# Capstone_Preconditioning_SchematicSheet.net
KiCad netlist of a schematic drawn in Altium Designer
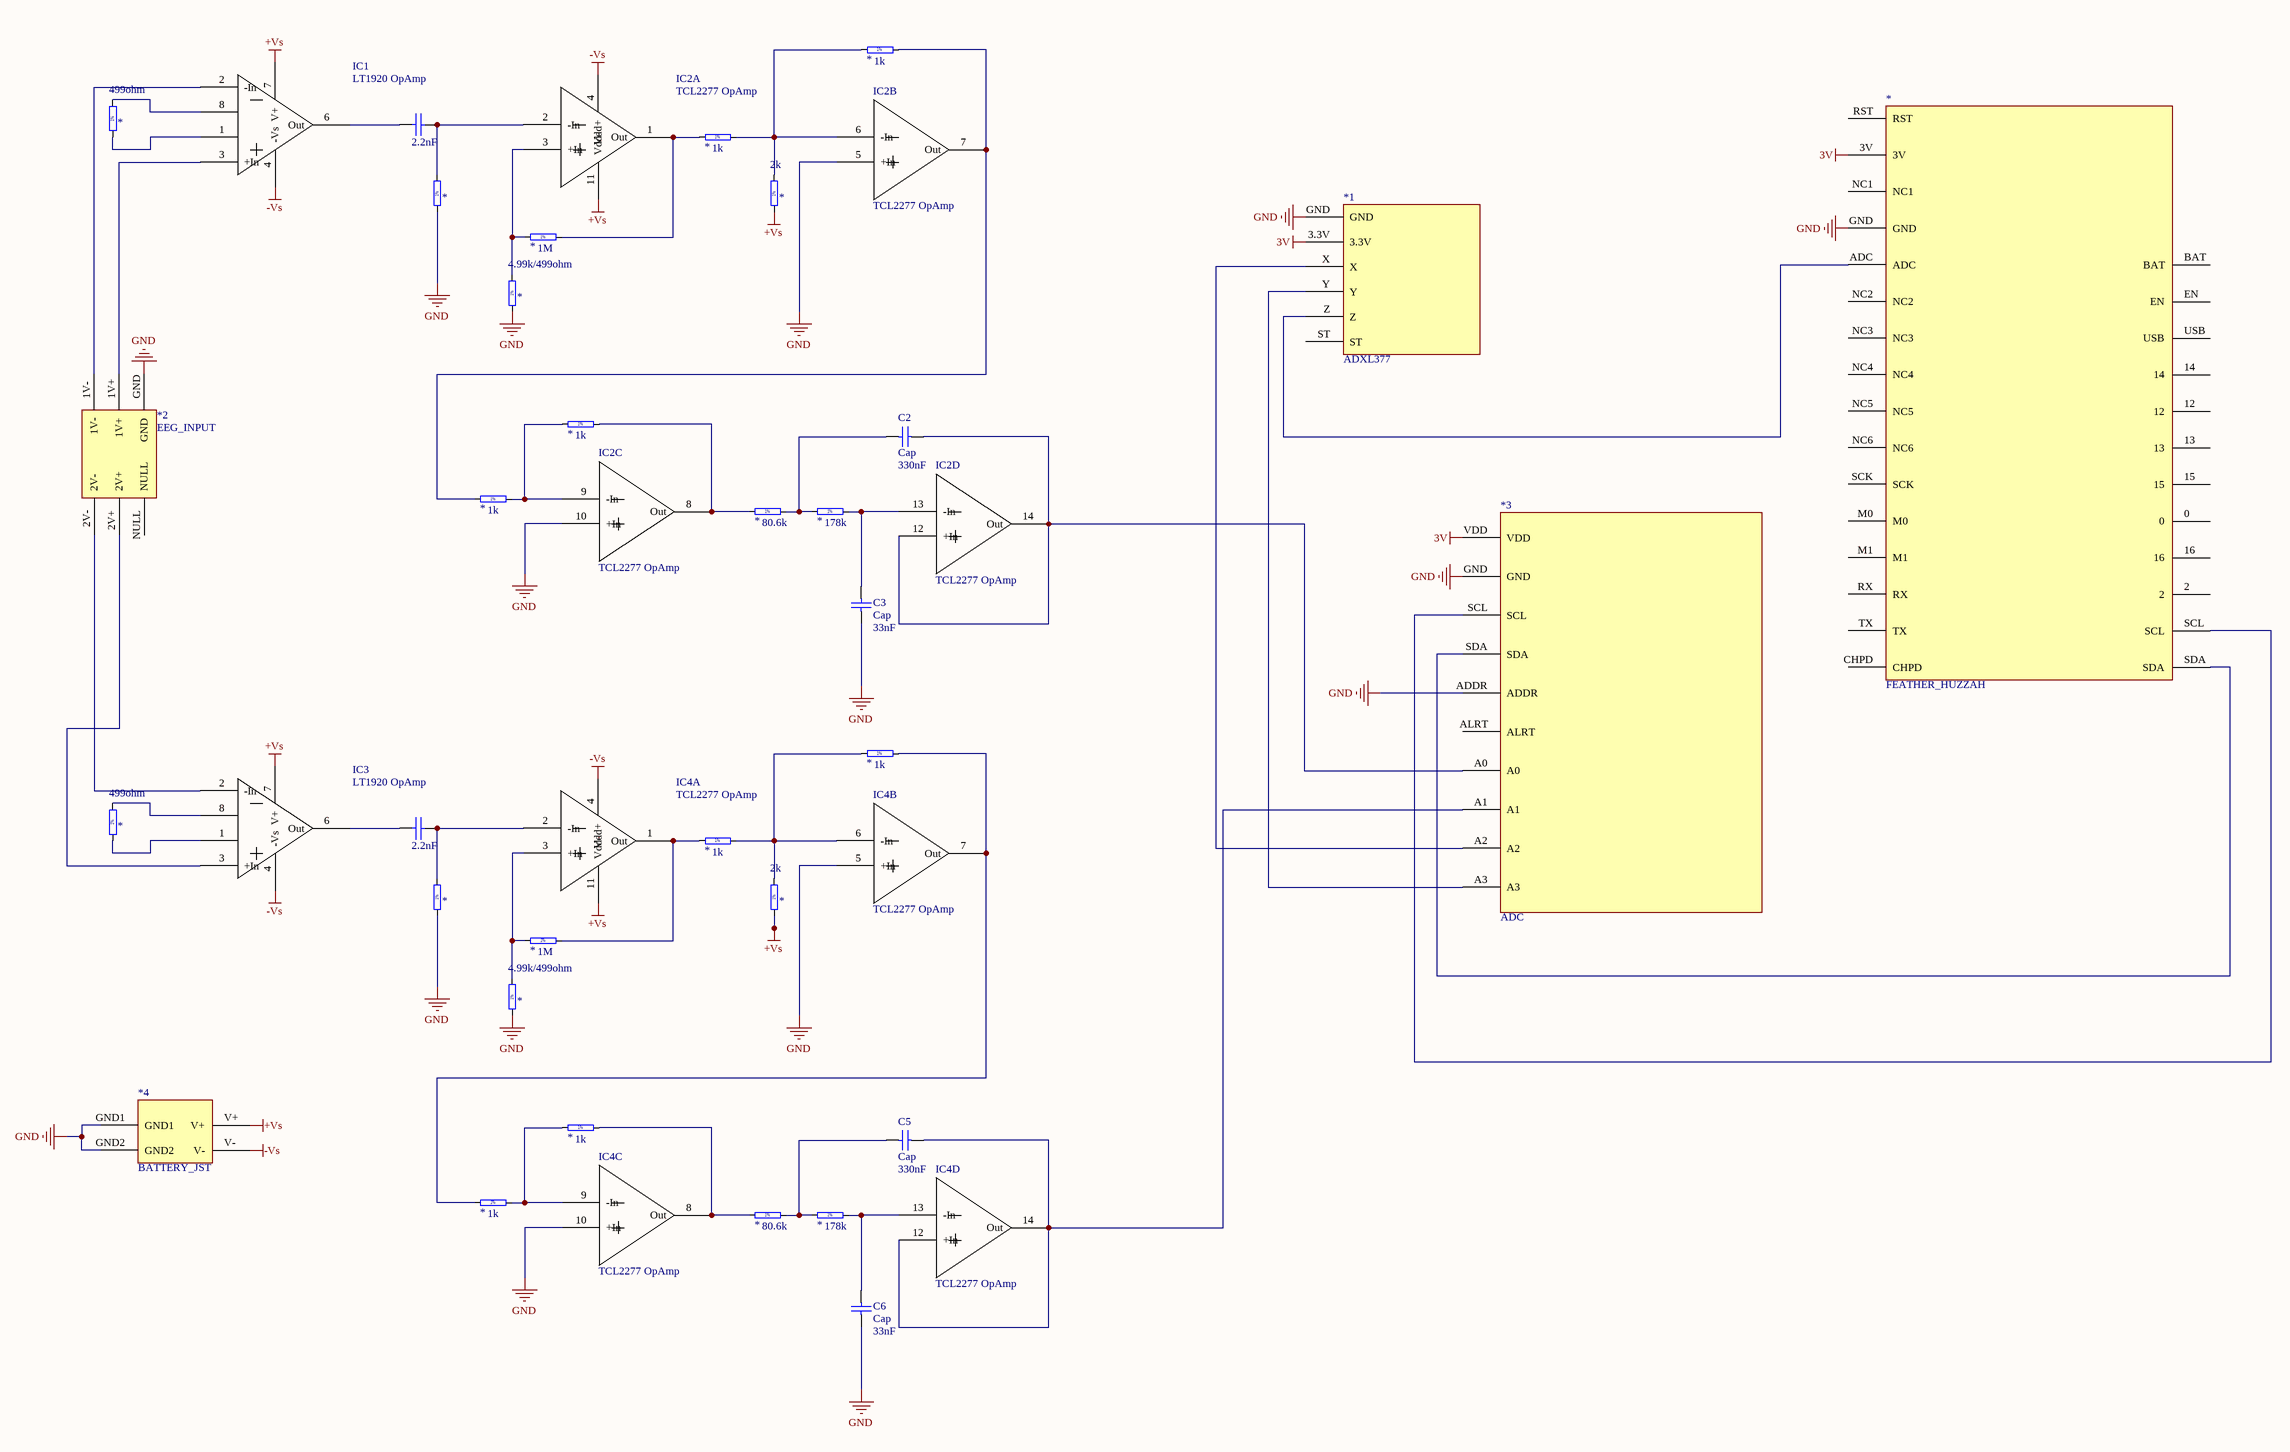
[diagram p0: Capstone_Preconditioning_SchematicSheet.SchDoc]

(export (version "E")
  (design (tool "Eeschema 10.0.6"))
  (components
    (comp (ref "*")
      (value "FEATHER_HUZZAH")
      (footprint "Feather_Huzzah")
      (libsource (lib "CustomComponentsLibrary") (part "FEATHER_HUZZAH"))
    )
    (comp (ref "*1")
      (value "ADXL377")
      (footprint "ADXL377_Acc")
      (libsource (lib "CustomComponentsLibrary") (part "ADXL377"))
    )
    (comp (ref "*2") (value "EEG_INPUT") (libsource (lib "CustomComponentsLibrary") (part "EEG_INPUT")))
    (comp (ref "*3") (value "ADC") (footprint "ADC") (libsource (lib "CustomComponentsLibrary") (part "ADC")))
    (comp (ref "*4")
      (value "BATTERY_JST")
      (footprint "BATTERY_JST")
      (libsource (lib "CustomComponentsLibrary") (part "BATTERY_JST"))
    )
    (comp (ref "C1")
      (value "2.2nF")
      (footprint "CAP_0603")
      (libsource (lib "NEUDOSE-Components") (part "CAP SEMI MLCC"))
    )
    (comp (ref "C2")
      (value "Cap")
      (footprint "CAP_0603")
      (description "Capacitor")
      (fields (field (name "ALTIUM_VALUE") "330nF") (field (name "PUBLISHER") "Altium Limited"))
      (libsource (lib "Miscellaneous Devices") (part "Cap"))
    )
    (comp (ref "C3")
      (value "Cap")
      (footprint "CAP_0603")
      (description "Capacitor")
      (fields (field (name "ALTIUM_VALUE") "33nF") (field (name "PUBLISHER") "Altium Limited"))
      (libsource (lib "Miscellaneous Devices") (part "Cap"))
    )
    (comp (ref "C4")
      (value "2.2nF")
      (footprint "CAP_0603")
      (libsource (lib "NEUDOSE-Components") (part "CAP SEMI MLCC"))
    )
    (comp (ref "C5")
      (value "Cap")
      (footprint "CAP_0603")
      (description "Capacitor")
      (fields (field (name "ALTIUM_VALUE") "330nF") (field (name "PUBLISHER") "Altium Limited"))
      (libsource (lib "Miscellaneous Devices") (part "Cap"))
    )
    (comp (ref "C6")
      (value "Cap")
      (footprint "CAP_0603")
      (description "Capacitor")
      (fields (field (name "ALTIUM_VALUE") "33nF") (field (name "PUBLISHER") "Altium Limited"))
      (libsource (lib "Miscellaneous Devices") (part "Cap"))
    )
    (comp (ref "IC1")
      (value "LT1920 OpAmp")
      (footprint "LT1920")
      (libsource (lib "CustomComponentsLibrary") (part "LT1920 OpAmp"))
    )
    (comp (ref "IC2")
      (value "TCL2277 OpAmp")
      (footprint "TLC2277")
      (libsource (lib "CustomComponentsLibrary") (part "TCL2277"))
    )
    (comp (ref "IC3")
      (value "LT1920 OpAmp")
      (footprint "LT1920")
      (libsource (lib "CustomComponentsLibrary") (part "LT1920 OpAmp"))
    )
    (comp (ref "IC4")
      (value "TCL2277 OpAmp")
      (footprint "TLC2277")
      (libsource (lib "CustomComponentsLibrary") (part "TCL2277"))
    )
    (comp (ref "R1")
      (value "1k")
      (footprint "RES_0603")
      (description "1.0%")
      (fields (field (name "ALTIUM_VALUE") "*"))
      (libsource (lib "NEUDOSE-Components") (part "RES SEMI (1.0%)"))
    )
    (comp (ref "R2")
      (value "499ohm")
      (footprint "RES_0603")
      (description "1.0%")
      (fields (field (name "ALTIUM_VALUE") "*"))
      (libsource (lib "NEUDOSE-Components") (part "RES SEMI (1.0%)"))
    )
    (comp (ref "R3")
      (value "1k")
      (footprint "RES_0603")
      (description "1.0%")
      (fields (field (name "ALTIUM_VALUE") "*"))
      (libsource (lib "NEUDOSE-Components") (part "RES SEMI (1.0%)"))
    )
    (comp (ref "R4")
      (value "71.5k")
      (footprint "RES_0603")
      (description "1.0%")
      (fields (field (name "ALTIUM_VALUE") "*"))
      (libsource (lib "NEUDOSE-Components") (part "RES SEMI (1.0%)"))
    )
    (comp (ref "R5")
      (value "2k")
      (footprint "RES_0603")
      (description "1.0%")
      (fields (field (name "ALTIUM_VALUE") "*"))
      (libsource (lib "NEUDOSE-Components") (part "RES SEMI (1.0%)"))
    )
    (comp (ref "R6")
      (value "1M")
      (footprint "RES_0603")
      (description "1.0%")
      (fields (field (name "ALTIUM_VALUE") "*"))
      (libsource (lib "NEUDOSE-Components") (part "RES SEMI (1.0%)"))
    )
    (comp (ref "R7")
      (value "4.99k/499ohm")
      (footprint "RES_0603")
      (description "1.0%")
      (fields (field (name "ALTIUM_VALUE") "*"))
      (libsource (lib "NEUDOSE-Components") (part "RES SEMI (1.0%)"))
    )
    (comp (ref "R8")
      (value "1k")
      (footprint "RES_0603")
      (description "1.0%")
      (fields (field (name "ALTIUM_VALUE") "*"))
      (libsource (lib "NEUDOSE-Components") (part "RES SEMI (1.0%)"))
    )
    (comp (ref "R9")
      (value "1k")
      (footprint "RES_0603")
      (description "1.0%")
      (fields (field (name "ALTIUM_VALUE") "*"))
      (libsource (lib "NEUDOSE-Components") (part "RES SEMI (1.0%)"))
    )
    (comp (ref "R10")
      (value "80.6k")
      (footprint "RES_0603")
      (description "1.0%")
      (fields (field (name "ALTIUM_VALUE") "*"))
      (libsource (lib "NEUDOSE-Components") (part "RES SEMI (1.0%)"))
    )
    (comp (ref "R11")
      (value "178k")
      (footprint "RES_0603")
      (description "1.0%")
      (fields (field (name "ALTIUM_VALUE") "*"))
      (libsource (lib "NEUDOSE-Components") (part "RES SEMI (1.0%)"))
    )
    (comp (ref "R12")
      (value "1k")
      (footprint "RES_0603")
      (description "1.0%")
      (fields (field (name "ALTIUM_VALUE") "*"))
      (libsource (lib "NEUDOSE-Components") (part "RES SEMI (1.0%)"))
    )
    (comp (ref "R13")
      (value "499ohm")
      (footprint "RES_0603")
      (description "1.0%")
      (fields (field (name "ALTIUM_VALUE") "*"))
      (libsource (lib "NEUDOSE-Components") (part "RES SEMI (1.0%)"))
    )
    (comp (ref "R14")
      (value "1k")
      (footprint "RES_0603")
      (description "1.0%")
      (fields (field (name "ALTIUM_VALUE") "*"))
      (libsource (lib "NEUDOSE-Components") (part "RES SEMI (1.0%)"))
    )
    (comp (ref "R15")
      (value "71.5k")
      (footprint "RES_0603")
      (description "1.0%")
      (fields (field (name "ALTIUM_VALUE") "*"))
      (libsource (lib "NEUDOSE-Components") (part "RES SEMI (1.0%)"))
    )
    (comp (ref "R16")
      (value "2k")
      (footprint "RES_0603")
      (description "1.0%")
      (fields (field (name "ALTIUM_VALUE") "*"))
      (libsource (lib "NEUDOSE-Components") (part "RES SEMI (1.0%)"))
    )
    (comp (ref "R17")
      (value "1M")
      (footprint "RES_0603")
      (description "1.0%")
      (fields (field (name "ALTIUM_VALUE") "*"))
      (libsource (lib "NEUDOSE-Components") (part "RES SEMI (1.0%)"))
    )
    (comp (ref "R18")
      (value "4.99k/499ohm")
      (footprint "RES_0603")
      (description "1.0%")
      (fields (field (name "ALTIUM_VALUE") "*"))
      (libsource (lib "NEUDOSE-Components") (part "RES SEMI (1.0%)"))
    )
    (comp (ref "R19")
      (value "1k")
      (footprint "RES_0603")
      (description "1.0%")
      (fields (field (name "ALTIUM_VALUE") "*"))
      (libsource (lib "NEUDOSE-Components") (part "RES SEMI (1.0%)"))
    )
    (comp (ref "R20")
      (value "1k")
      (footprint "RES_0603")
      (description "1.0%")
      (fields (field (name "ALTIUM_VALUE") "*"))
      (libsource (lib "NEUDOSE-Components") (part "RES SEMI (1.0%)"))
    )
    (comp (ref "R21")
      (value "80.6k")
      (footprint "RES_0603")
      (description "1.0%")
      (fields (field (name "ALTIUM_VALUE") "*"))
      (libsource (lib "NEUDOSE-Components") (part "RES SEMI (1.0%)"))
    )
    (comp (ref "R22")
      (value "178k")
      (footprint "RES_0603")
      (description "1.0%")
      (fields (field (name "ALTIUM_VALUE") "*"))
      (libsource (lib "NEUDOSE-Components") (part "RES SEMI (1.0%)"))
    )
  )
  (nets
    (net (code "1") (name "+Vs") (class "Default")
      (node (ref "*4") (pin "V+") (pinfunction "V+_V+") (pintype "passive"))
      (node (ref "IC1") (pin "7") (pinfunction "V+_7") (pintype "passive"))
      (node (ref "IC2") (pin "11") (pinfunction "Vdd-_11") (pintype "passive"))
      (node (ref "IC3") (pin "7") (pinfunction "V+_7") (pintype "passive"))
      (node (ref "IC4") (pin "11") (pinfunction "Vdd-_11") (pintype "passive"))
      (node (ref "R16") (pin "1") (pintype "passive"))
      (node (ref "R5") (pin "1") (pintype "passive"))
    )
    (net (code "2") (name "-Vs") (class "Default")
      (node (ref "*4") (pin "V-") (pinfunction "V-_V-") (pintype "passive"))
      (node (ref "IC1") (pin "4") (pinfunction "-Vs_4") (pintype "passive"))
      (node (ref "IC2") (pin "4") (pinfunction "Vdd+_4") (pintype "passive"))
      (node (ref "IC3") (pin "4") (pinfunction "-Vs_4") (pintype "passive"))
      (node (ref "IC4") (pin "4") (pinfunction "Vdd+_4") (pintype "passive"))
    )
    (net (code "3") (name "3V") (class "Default")
      (node (ref "*") (pin "3V") (pinfunction "3V_3V") (pintype "passive"))
      (node (ref "*1") (pin "3.3V") (pinfunction "3.3V_3.3V") (pintype "passive"))
      (node (ref "*3") (pin "VDD") (pinfunction "VDD_VDD") (pintype "passive"))
    )
    (net (code "4") (name "GND") (class "Default")
      (node (ref "*") (pin "GND") (pinfunction "GND_GND") (pintype "passive"))
      (node (ref "*1") (pin "GND") (pinfunction "GND_GND") (pintype "passive"))
      (node (ref "*2") (pin "GND") (pinfunction "GND_GND") (pintype "passive"))
      (node (ref "*3") (pin "ADDR") (pinfunction "ADDR_ADDR") (pintype "passive"))
      (node (ref "*3") (pin "GND") (pinfunction "GND_GND") (pintype "passive"))
      (node (ref "*4") (pin "GND1") (pinfunction "GND1_GND1") (pintype "passive"))
      (node (ref "*4") (pin "GND2") (pinfunction "GND2_GND2") (pintype "passive"))
      (node (ref "C3") (pin "1") (pinfunction "1_1") (pintype "passive"))
      (node (ref "C6") (pin "1") (pinfunction "1_1") (pintype "passive"))
      (node (ref "IC2") (pin "10") (pinfunction "+In_10") (pintype "passive"))
      (node (ref "IC2") (pin "5") (pinfunction "+In_5") (pintype "passive"))
      (node (ref "IC4") (pin "10") (pinfunction "+In_10") (pintype "passive"))
      (node (ref "IC4") (pin "5") (pinfunction "+In_5") (pintype "passive"))
      (node (ref "R15") (pin "1") (pintype "passive"))
      (node (ref "R18") (pin "1") (pintype "passive"))
      (node (ref "R4") (pin "1") (pintype "passive"))
      (node (ref "R7") (pin "1") (pintype "passive"))
    )
    (net (code "5") (name "Net-(*-PadADC)") (class "Default")
      (node (ref "*") (pin "ADC") (pinfunction "ADC_ADC") (pintype "passive"))
      (node (ref "*1") (pin "Z") (pinfunction "Z_Z") (pintype "passive"))
    )
    (net (code "6") (name "Net-(*-PadSCL)") (class "Default")
      (node (ref "*") (pin "SCL") (pinfunction "SCL_SCL") (pintype "passive"))
      (node (ref "*3") (pin "SCL") (pinfunction "SCL_SCL") (pintype "passive"))
    )
    (net (code "7") (name "Net-(*-PadSDA)") (class "Default")
      (node (ref "*") (pin "SDA") (pinfunction "SDA_SDA") (pintype "passive"))
      (node (ref "*3") (pin "SDA") (pinfunction "SDA_SDA") (pintype "passive"))
    )
    (net (code "8") (name "Net-(*1-PadX)") (class "Default")
      (node (ref "*1") (pin "X") (pinfunction "X_X") (pintype "passive"))
      (node (ref "*3") (pin "A2") (pinfunction "A2_A2") (pintype "passive"))
    )
    (net (code "9") (name "Net-(*1-PadY)") (class "Default")
      (node (ref "*1") (pin "Y") (pinfunction "Y_Y") (pintype "passive"))
      (node (ref "*3") (pin "A3") (pinfunction "A3_A3") (pintype "passive"))
    )
    (net (code "10") (name "Net-(C2-Pad2)") (class "Default")
      (node (ref "C2") (pin "2") (pinfunction "2_2") (pintype "passive"))
      (node (ref "R10") (pin "2") (pintype "passive"))
      (node (ref "R11") (pin "1") (pintype "passive"))
    )
    (net (code "11") (name "Net-(C5-Pad2)") (class "Default")
      (node (ref "C5") (pin "2") (pinfunction "2_2") (pintype "passive"))
      (node (ref "R21") (pin "2") (pintype "passive"))
      (node (ref "R22") (pin "1") (pintype "passive"))
    )
    (net (code "12") (name "Net-(IC1-+In)") (class "Default")
      (node (ref "*2") (pin "1V+") (pinfunction "1V+_1V+") (pintype "passive"))
      (node (ref "IC1") (pin "3") (pinfunction "+In_3") (pintype "passive"))
    )
    (net (code "13") (name "Net-(IC1--In)") (class "Default")
      (node (ref "*2") (pin "1V-") (pinfunction "1V-_1V-") (pintype "passive"))
      (node (ref "IC1") (pin "2") (pinfunction "-In_2") (pintype "passive"))
    )
    (net (code "14") (name "Net-(IC1-Out)") (class "Default")
      (node (ref "C1") (pin "1") (pintype "passive"))
      (node (ref "IC1") (pin "6") (pinfunction "Out_6") (pintype "passive"))
    )
    (net (code "15") (name "Net-(IC1-Rg-Pad1)") (class "Default")
      (node (ref "IC1") (pin "1") (pinfunction "Rg_1") (pintype "passive"))
      (node (ref "R2") (pin "1") (pintype "passive"))
    )
    (net (code "16") (name "Net-(IC1-Rg-Pad8)") (class "Default")
      (node (ref "IC1") (pin "8") (pinfunction "Rg_8") (pintype "passive"))
      (node (ref "R2") (pin "2") (pintype "passive"))
    )
    (net (code "17") (name "Net-(IC2A-+In)") (class "Default")
      (node (ref "IC2") (pin "3") (pinfunction "+In_3") (pintype "passive"))
      (node (ref "R6") (pin "1") (pintype "passive"))
      (node (ref "R7") (pin "2") (pintype "passive"))
    )
    (net (code "18") (name "Net-(IC2A--In)") (class "Default")
      (node (ref "C1") (pin "2") (pintype "passive"))
      (node (ref "IC2") (pin "2") (pinfunction "-In_2") (pintype "passive"))
      (node (ref "R4") (pin "2") (pintype "passive"))
    )
    (net (code "19") (name "Net-(IC2A-Out)") (class "Default")
      (node (ref "IC2") (pin "1") (pinfunction "Out_1") (pintype "passive"))
      (node (ref "R3") (pin "1") (pintype "passive"))
      (node (ref "R6") (pin "2") (pintype "passive"))
    )
    (net (code "20") (name "Net-(IC2B--In)") (class "Default")
      (node (ref "IC2") (pin "6") (pinfunction "-In_6") (pintype "passive"))
      (node (ref "R1") (pin "1") (pintype "passive"))
      (node (ref "R3") (pin "2") (pintype "passive"))
      (node (ref "R5") (pin "2") (pintype "passive"))
    )
    (net (code "21") (name "Net-(IC2B-Out)") (class "Default")
      (node (ref "IC2") (pin "7") (pinfunction "Out_7") (pintype "passive"))
      (node (ref "R1") (pin "2") (pintype "passive"))
      (node (ref "R9") (pin "1") (pintype "passive"))
    )
    (net (code "22") (name "Net-(IC2C--In)") (class "Default")
      (node (ref "IC2") (pin "9") (pinfunction "-In_9") (pintype "passive"))
      (node (ref "R8") (pin "1") (pintype "passive"))
      (node (ref "R9") (pin "2") (pintype "passive"))
    )
    (net (code "23") (name "Net-(IC2C-Out)") (class "Default")
      (node (ref "IC2") (pin "8") (pinfunction "Out_8") (pintype "passive"))
      (node (ref "R10") (pin "1") (pintype "passive"))
      (node (ref "R8") (pin "2") (pintype "passive"))
    )
    (net (code "24") (name "Net-(IC2D-+In)") (class "Default")
      (node (ref "*3") (pin "A0") (pinfunction "A0_A0") (pintype "passive"))
      (node (ref "C2") (pin "1") (pinfunction "1_1") (pintype "passive"))
      (node (ref "IC2") (pin "12") (pinfunction "+In_12") (pintype "passive"))
      (node (ref "IC2") (pin "14") (pinfunction "Out_14") (pintype "passive"))
    )
    (net (code "25") (name "Net-(IC2D--In)") (class "Default")
      (node (ref "C3") (pin "2") (pinfunction "2_2") (pintype "passive"))
      (node (ref "IC2") (pin "13") (pinfunction "-In_13") (pintype "passive"))
      (node (ref "R11") (pin "2") (pintype "passive"))
    )
    (net (code "26") (name "Net-(IC3-+In)") (class "Default")
      (node (ref "*2") (pin "2V+") (pinfunction "2V+_2V+") (pintype "passive"))
      (node (ref "IC3") (pin "3") (pinfunction "+In_3") (pintype "passive"))
    )
    (net (code "27") (name "Net-(IC3--In)") (class "Default")
      (node (ref "*2") (pin "2V-") (pinfunction "2V-_2V-") (pintype "passive"))
      (node (ref "IC3") (pin "2") (pinfunction "-In_2") (pintype "passive"))
    )
    (net (code "28") (name "Net-(IC3-Out)") (class "Default")
      (node (ref "C4") (pin "1") (pintype "passive"))
      (node (ref "IC3") (pin "6") (pinfunction "Out_6") (pintype "passive"))
    )
    (net (code "29") (name "Net-(IC3-Rg-Pad1)") (class "Default")
      (node (ref "IC3") (pin "1") (pinfunction "Rg_1") (pintype "passive"))
      (node (ref "R13") (pin "1") (pintype "passive"))
    )
    (net (code "30") (name "Net-(IC3-Rg-Pad8)") (class "Default")
      (node (ref "IC3") (pin "8") (pinfunction "Rg_8") (pintype "passive"))
      (node (ref "R13") (pin "2") (pintype "passive"))
    )
    (net (code "31") (name "Net-(IC4A-+In)") (class "Default")
      (node (ref "IC4") (pin "3") (pinfunction "+In_3") (pintype "passive"))
      (node (ref "R17") (pin "1") (pintype "passive"))
      (node (ref "R18") (pin "2") (pintype "passive"))
    )
    (net (code "32") (name "Net-(IC4A--In)") (class "Default")
      (node (ref "C4") (pin "2") (pintype "passive"))
      (node (ref "IC4") (pin "2") (pinfunction "-In_2") (pintype "passive"))
      (node (ref "R15") (pin "2") (pintype "passive"))
    )
    (net (code "33") (name "Net-(IC4A-Out)") (class "Default")
      (node (ref "IC4") (pin "1") (pinfunction "Out_1") (pintype "passive"))
      (node (ref "R14") (pin "1") (pintype "passive"))
      (node (ref "R17") (pin "2") (pintype "passive"))
    )
    (net (code "34") (name "Net-(IC4B--In)") (class "Default")
      (node (ref "IC4") (pin "6") (pinfunction "-In_6") (pintype "passive"))
      (node (ref "R12") (pin "1") (pintype "passive"))
      (node (ref "R14") (pin "2") (pintype "passive"))
      (node (ref "R16") (pin "2") (pintype "passive"))
    )
    (net (code "35") (name "Net-(IC4B-Out)") (class "Default")
      (node (ref "IC4") (pin "7") (pinfunction "Out_7") (pintype "passive"))
      (node (ref "R12") (pin "2") (pintype "passive"))
      (node (ref "R20") (pin "1") (pintype "passive"))
    )
    (net (code "36") (name "Net-(IC4C--In)") (class "Default")
      (node (ref "IC4") (pin "9") (pinfunction "-In_9") (pintype "passive"))
      (node (ref "R19") (pin "1") (pintype "passive"))
      (node (ref "R20") (pin "2") (pintype "passive"))
    )
    (net (code "37") (name "Net-(IC4C-Out)") (class "Default")
      (node (ref "IC4") (pin "8") (pinfunction "Out_8") (pintype "passive"))
      (node (ref "R19") (pin "2") (pintype "passive"))
      (node (ref "R21") (pin "1") (pintype "passive"))
    )
    (net (code "38") (name "Net-(IC4D-+In)") (class "Default")
      (node (ref "*3") (pin "A1") (pinfunction "A1_A1") (pintype "passive"))
      (node (ref "C5") (pin "1") (pinfunction "1_1") (pintype "passive"))
      (node (ref "IC4") (pin "12") (pinfunction "+In_12") (pintype "passive"))
      (node (ref "IC4") (pin "14") (pinfunction "Out_14") (pintype "passive"))
    )
    (net (code "39") (name "Net-(IC4D--In)") (class "Default")
      (node (ref "C6") (pin "2") (pinfunction "2_2") (pintype "passive"))
      (node (ref "IC4") (pin "13") (pinfunction "-In_13") (pintype "passive"))
      (node (ref "R22") (pin "2") (pintype "passive"))
    )
    (net (code "40") (name "unconnected-(*-Pad0)") (class "Default")
      (node (ref "*") (pin "0") (pinfunction "0_0") (pintype "passive"))
    )
    (net (code "41") (name "unconnected-(*-Pad2)") (class "Default")
      (node (ref "*") (pin "2") (pinfunction "2_2") (pintype "passive"))
    )
    (net (code "42") (name "unconnected-(*-Pad12)") (class "Default")
      (node (ref "*") (pin "12") (pinfunction "12_12") (pintype "passive"))
    )
    (net (code "43") (name "unconnected-(*-Pad13)") (class "Default")
      (node (ref "*") (pin "13") (pinfunction "13_13") (pintype "passive"))
    )
    (net (code "44") (name "unconnected-(*-Pad14)") (class "Default")
      (node (ref "*") (pin "14") (pinfunction "14_14") (pintype "passive"))
    )
    (net (code "45") (name "unconnected-(*-Pad15)") (class "Default")
      (node (ref "*") (pin "15") (pinfunction "15_15") (pintype "passive"))
    )
    (net (code "46") (name "unconnected-(*-Pad16)") (class "Default")
      (node (ref "*") (pin "16") (pinfunction "16_16") (pintype "passive"))
    )
    (net (code "47") (name "unconnected-(*-PadBAT)") (class "Default")
      (node (ref "*") (pin "BAT") (pinfunction "BAT_BAT") (pintype "passive"))
    )
    (net (code "48") (name "unconnected-(*-PadCHPD)") (class "Default")
      (node (ref "*") (pin "CHPD") (pinfunction "CHPD_CHPD") (pintype "passive"))
    )
    (net (code "49") (name "unconnected-(*-PadEN)") (class "Default")
      (node (ref "*") (pin "EN") (pinfunction "EN_EN") (pintype "passive"))
    )
    (net (code "50") (name "unconnected-(*-PadM0)") (class "Default")
      (node (ref "*") (pin "M0") (pinfunction "M0_M0") (pintype "passive"))
    )
    (net (code "51") (name "unconnected-(*-PadM1)") (class "Default")
      (node (ref "*") (pin "M1") (pinfunction "M1_M1") (pintype "passive"))
    )
    (net (code "52") (name "unconnected-(*-PadNC1)") (class "Default")
      (node (ref "*") (pin "NC1") (pinfunction "NC1_NC1") (pintype "passive"))
    )
    (net (code "53") (name "unconnected-(*-PadNC2)") (class "Default")
      (node (ref "*") (pin "NC2") (pinfunction "NC2_NC2") (pintype "passive"))
    )
    (net (code "54") (name "unconnected-(*-PadNC3)") (class "Default")
      (node (ref "*") (pin "NC3") (pinfunction "NC3_NC3") (pintype "passive"))
    )
    (net (code "55") (name "unconnected-(*-PadNC4)") (class "Default")
      (node (ref "*") (pin "NC4") (pinfunction "NC4_NC4") (pintype "passive"))
    )
    (net (code "56") (name "unconnected-(*-PadNC5)") (class "Default")
      (node (ref "*") (pin "NC5") (pinfunction "NC5_NC5") (pintype "passive"))
    )
    (net (code "57") (name "unconnected-(*-PadNC6)") (class "Default")
      (node (ref "*") (pin "NC6") (pinfunction "NC6_NC6") (pintype "passive"))
    )
    (net (code "58") (name "unconnected-(*-PadRST)") (class "Default")
      (node (ref "*") (pin "RST") (pinfunction "RST_RST") (pintype "passive"))
    )
    (net (code "59") (name "unconnected-(*-PadRX)") (class "Default")
      (node (ref "*") (pin "RX") (pinfunction "RX_RX") (pintype "passive"))
    )
    (net (code "60") (name "unconnected-(*-PadSCK)") (class "Default")
      (node (ref "*") (pin "SCK") (pinfunction "SCK_SCK") (pintype "passive"))
    )
    (net (code "61") (name "unconnected-(*-PadTX)") (class "Default")
      (node (ref "*") (pin "TX") (pinfunction "TX_TX") (pintype "passive"))
    )
    (net (code "62") (name "unconnected-(*-PadUSB)") (class "Default")
      (node (ref "*") (pin "USB") (pinfunction "USB_USB") (pintype "passive"))
    )
    (net (code "63") (name "unconnected-(*1-PadST)") (class "Default")
      (node (ref "*1") (pin "ST") (pinfunction "ST_ST") (pintype "passive"))
    )
    (net (code "64") (name "unconnected-(*2-PadNULL)") (class "Default")
      (node (ref "*2") (pin "NULL") (pinfunction "NULL_NULL") (pintype "passive"))
    )
    (net (code "65") (name "unconnected-(*3-PadALRT)") (class "Default")
      (node (ref "*3") (pin "ALRT") (pinfunction "ALRT_ALRT") (pintype "passive"))
    )
  )
)
